# XTXBoard_2CPU.net
KiCad netlist of a schematic drawn in Altium Designer
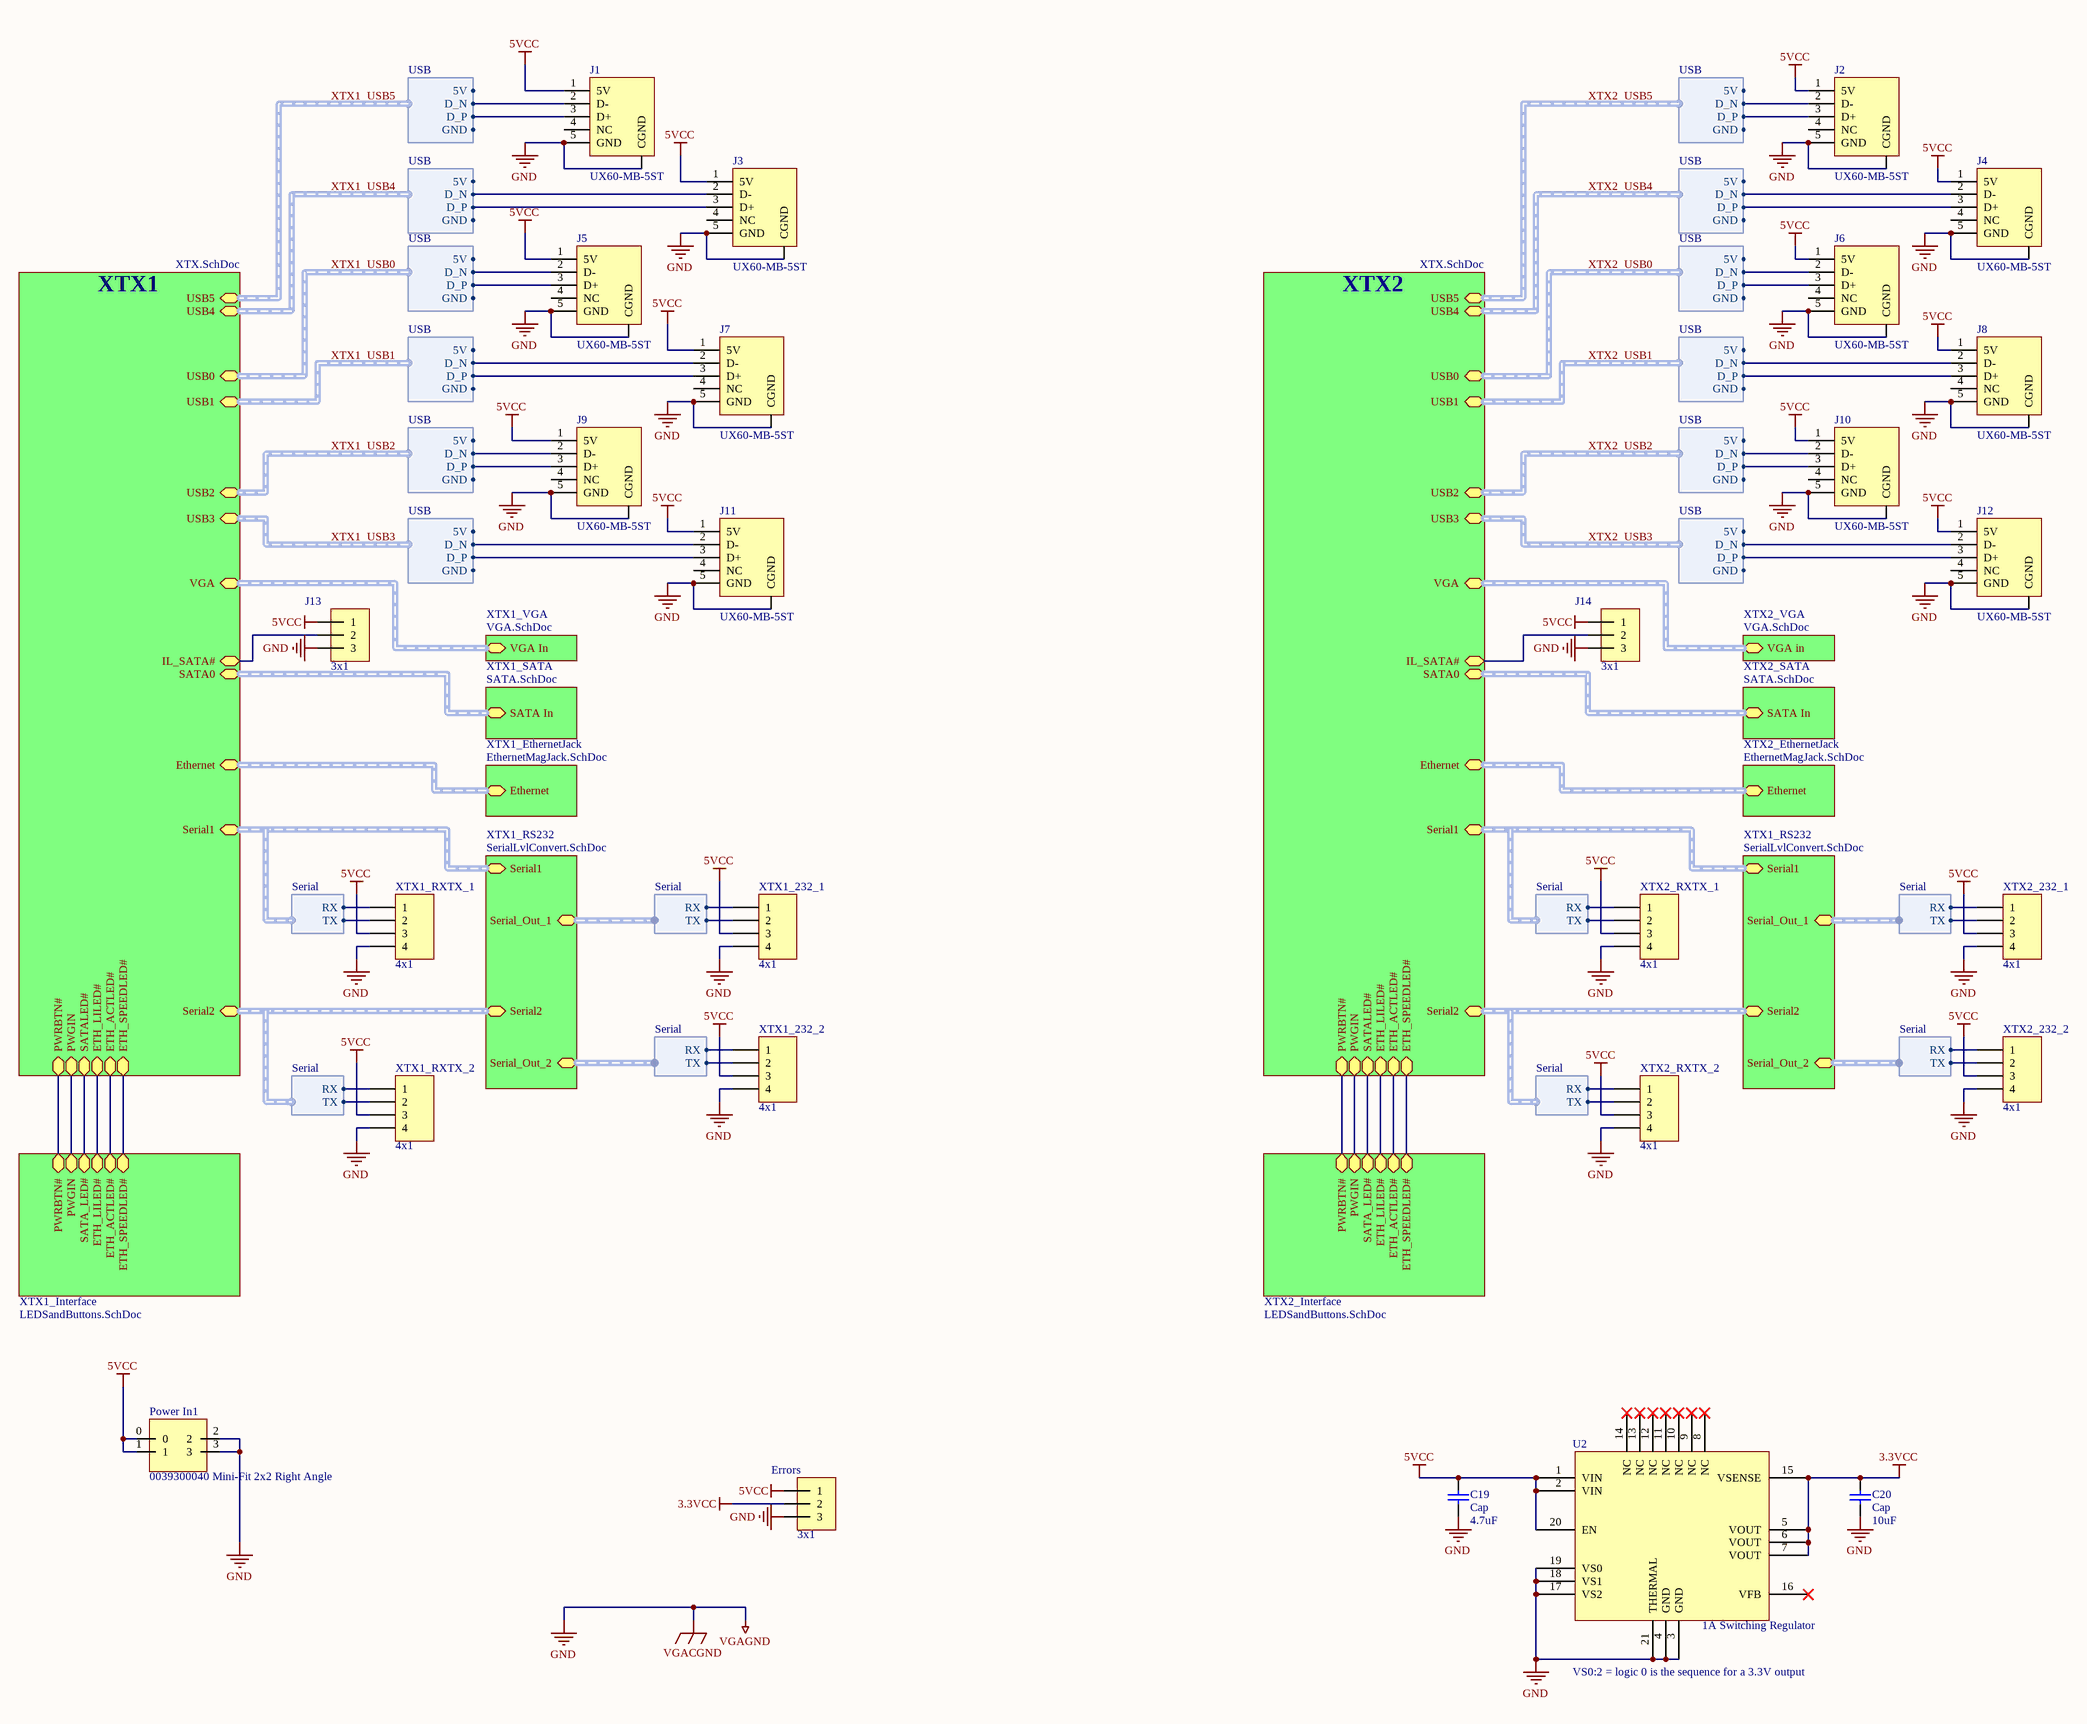
[diagram p0: XTXBoard(2CPU).SchDoc]

(export (version "E")
  (design (tool "Eeschema 10.0.6"))
  (components
    (comp (ref "C19")
      (value "Cap")
      (footprint "PassiveComponents:0805 (2012) Capacitor")
      (description "Capacitor")
      (fields (field (name "ALTIUM_VALUE") "4.7uF") (field (name "PUBLISHER") "Altium Limited"))
      (libsource (lib "Miscellaneous Devices") (part "Cap"))
    )
    (comp (ref "C20")
      (value "Cap")
      (footprint "PassiveComponents:1210 (3225) Capacitor")
      (description "Capacitor")
      (fields (field (name "ALTIUM_VALUE") "10uF") (field (name "PUBLISHER") "Altium Limited"))
      (libsource (lib "Miscellaneous Devices") (part "Cap"))
    )
    (comp (ref "Errors")
      (value "3x1")
      (footprint "Headers:Male 3x1")
      (description "3x1 100mil Header")
      (libsource (lib "Headers") (part "3x1"))
    )
    (comp (ref "J1")
      (value "UX60-MB-5ST")
      (footprint "Hirose:UX60-MB-5ST")
      (description "miniUSB Type B SMT Connector")
      (libsource (lib "Hirose") (part "UX60-MB-5ST"))
    )
    (comp (ref "J2")
      (value "UX60-MB-5ST")
      (footprint "Hirose:UX60-MB-5ST")
      (description "miniUSB Type B SMT Connector")
      (libsource (lib "Hirose") (part "UX60-MB-5ST"))
    )
    (comp (ref "J3")
      (value "UX60-MB-5ST")
      (footprint "Hirose:UX60-MB-5ST")
      (description "miniUSB Type B SMT Connector")
      (libsource (lib "Hirose") (part "UX60-MB-5ST"))
    )
    (comp (ref "J4")
      (value "UX60-MB-5ST")
      (footprint "Hirose:UX60-MB-5ST")
      (description "miniUSB Type B SMT Connector")
      (libsource (lib "Hirose") (part "UX60-MB-5ST"))
    )
    (comp (ref "J5")
      (value "UX60-MB-5ST")
      (footprint "Hirose:UX60-MB-5ST")
      (description "miniUSB Type B SMT Connector")
      (libsource (lib "Hirose") (part "UX60-MB-5ST"))
    )
    (comp (ref "J6")
      (value "UX60-MB-5ST")
      (footprint "Hirose:UX60-MB-5ST")
      (description "miniUSB Type B SMT Connector")
      (libsource (lib "Hirose") (part "UX60-MB-5ST"))
    )
    (comp (ref "J7")
      (value "UX60-MB-5ST")
      (footprint "Hirose:UX60-MB-5ST")
      (description "miniUSB Type B SMT Connector")
      (libsource (lib "Hirose") (part "UX60-MB-5ST"))
    )
    (comp (ref "J8")
      (value "UX60-MB-5ST")
      (footprint "Hirose:UX60-MB-5ST")
      (description "miniUSB Type B SMT Connector")
      (libsource (lib "Hirose") (part "UX60-MB-5ST"))
    )
    (comp (ref "J9")
      (value "UX60-MB-5ST")
      (footprint "Hirose:UX60-MB-5ST")
      (description "miniUSB Type B SMT Connector")
      (libsource (lib "Hirose") (part "UX60-MB-5ST"))
    )
    (comp (ref "J10")
      (value "UX60-MB-5ST")
      (footprint "Hirose:UX60-MB-5ST")
      (description "miniUSB Type B SMT Connector")
      (libsource (lib "Hirose") (part "UX60-MB-5ST"))
    )
    (comp (ref "J11")
      (value "UX60-MB-5ST")
      (footprint "Hirose:UX60-MB-5ST")
      (description "miniUSB Type B SMT Connector")
      (libsource (lib "Hirose") (part "UX60-MB-5ST"))
    )
    (comp (ref "J12")
      (value "UX60-MB-5ST")
      (footprint "Hirose:UX60-MB-5ST")
      (description "miniUSB Type B SMT Connector")
      (libsource (lib "Hirose") (part "UX60-MB-5ST"))
    )
    (comp (ref "J13")
      (value "3x1")
      (footprint "Headers:Male 3x1")
      (description "3x1 100mil Header")
      (libsource (lib "Headers") (part "3x1"))
    )
    (comp (ref "J14")
      (value "3x1")
      (footprint "Male 3x1")
      (description "3x1 100mil Header")
      (libsource (lib "Headers") (part "3x1"))
    )
    (comp (ref "Power In1")
      (value "0039300040 Mini-Fit 2x2 Right Angle")
      (footprint "Molex:0039300040 MINI-FIT JR 4-Pos Right Angle")
      (libsource (lib "Molex") (part "0039300040 Mini-Fit 2x2 Right Angle"))
    )
    (comp (ref "U2")
      (value "1A Switching Regulator")
      (footprint "QFN65P400X500X80-20N")
      (description "1A Step Down Voltage Converter")
      (fields (field (name "MANUFACTURER 1 PART NUMBER") "EN5311QI"))
      (libsource (lib "Enpirion") (part "Component_1"))
    )
    (comp (ref "XTX1_232_1")
      (value "4x1")
      (footprint "Male 4x1")
      (description "Header, 4-Pin")
      (fields (field (name "PUBLISHER") "Altium Limited"))
      (libsource (lib "Miscellaneous Connectors") (part "Header 4"))
    )
    (comp (ref "XTX1_232_2")
      (value "4x1")
      (footprint "Male 4x1")
      (description "Header, 4-Pin")
      (fields (field (name "PUBLISHER") "Altium Limited"))
      (libsource (lib "Miscellaneous Connectors") (part "Header 4"))
    )
    (comp (ref "XTX1_RXTX_1")
      (value "4x1")
      (footprint "Headers:Male 4x1")
      (description "Header, 4-Pin")
      (fields (field (name "PUBLISHER") "Altium Limited"))
      (libsource (lib "Miscellaneous Connectors") (part "Header 4"))
    )
    (comp (ref "XTX1_RXTX_2")
      (value "4x1")
      (footprint "Male 4x1")
      (description "Header, 4-Pin")
      (fields (field (name "PUBLISHER") "Altium Limited"))
      (libsource (lib "Miscellaneous Connectors") (part "Header 4"))
    )
    (comp (ref "XTX2_232_1")
      (value "4x1")
      (footprint "Male 4x1")
      (description "Header, 4-Pin")
      (fields (field (name "PUBLISHER") "Altium Limited"))
      (libsource (lib "Miscellaneous Connectors") (part "Header 4"))
    )
    (comp (ref "XTX2_232_2")
      (value "4x1")
      (footprint "Male 4x1")
      (description "Header, 4-Pin")
      (fields (field (name "PUBLISHER") "Altium Limited"))
      (libsource (lib "Miscellaneous Connectors") (part "Header 4"))
    )
    (comp (ref "XTX2_RXTX_1")
      (value "4x1")
      (footprint "Male 4x1")
      (description "Header, 4-Pin")
      (fields (field (name "PUBLISHER") "Altium Limited"))
      (libsource (lib "Miscellaneous Connectors") (part "Header 4"))
    )
    (comp (ref "XTX2_RXTX_2")
      (value "4x1")
      (footprint "Male 4x1")
      (description "Header, 4-Pin")
      (fields (field (name "PUBLISHER") "Altium Limited"))
      (libsource (lib "Miscellaneous Connectors") (part "Header 4"))
    )
  )
  (nets
    (net (code "22") (name "/IL_SATA#") (class "Default")
      (node (ref "J13") (pin "2") (pinfunction "2_2") (pintype "passive"))
    )
    (net (code "23") (name "/IL_SATA#_1") (class "Default")
      (node (ref "J14") (pin "2") (pinfunction "2_2") (pintype "passive"))
    )
    (net (code "51") (name "3.3VCC") (class "Default")
      (node (ref "C20") (pin "2") (pinfunction "2_2") (pintype "passive"))
      (node (ref "Errors") (pin "2") (pinfunction "2_2") (pintype "passive"))
      (node (ref "U2") (pin "15") (pinfunction "VSENSE_15") (pintype "passive"))
      (node (ref "U2") (pin "5") (pinfunction "VOUT_5") (pintype "passive"))
      (node (ref "U2") (pin "6") (pinfunction "VOUT_6") (pintype "passive"))
      (node (ref "U2") (pin "7") (pinfunction "VOUT_7") (pintype "passive"))
    )
    (net (code "52") (name "5VCC") (class "Default")
      (node (ref "C19") (pin "2") (pinfunction "2_2") (pintype "passive"))
      (node (ref "Errors") (pin "1") (pinfunction "1_1") (pintype "passive"))
      (node (ref "J1") (pin "1") (pinfunction "5V_1") (pintype "passive"))
      (node (ref "J10") (pin "1") (pinfunction "5V_1") (pintype "passive"))
      (node (ref "J11") (pin "1") (pinfunction "5V_1") (pintype "passive"))
      (node (ref "J12") (pin "1") (pinfunction "5V_1") (pintype "passive"))
      (node (ref "J13") (pin "1") (pinfunction "1_1") (pintype "passive"))
      (node (ref "J14") (pin "1") (pinfunction "1_1") (pintype "passive"))
      (node (ref "J2") (pin "1") (pinfunction "5V_1") (pintype "passive"))
      (node (ref "J3") (pin "1") (pinfunction "5V_1") (pintype "passive"))
      (node (ref "J4") (pin "1") (pinfunction "5V_1") (pintype "passive"))
      (node (ref "J5") (pin "1") (pinfunction "5V_1") (pintype "passive"))
      (node (ref "J6") (pin "1") (pinfunction "5V_1") (pintype "passive"))
      (node (ref "J7") (pin "1") (pinfunction "5V_1") (pintype "passive"))
      (node (ref "J8") (pin "1") (pinfunction "5V_1") (pintype "passive"))
      (node (ref "J9") (pin "1") (pinfunction "5V_1") (pintype "passive"))
      (node (ref "Power In1") (pin "0") (pinfunction "0_0") (pintype "passive"))
      (node (ref "Power In1") (pin "1") (pinfunction "1_1") (pintype "passive"))
      (node (ref "U2") (pin "1") (pinfunction "VIN_1") (pintype "passive"))
      (node (ref "U2") (pin "2") (pinfunction "VIN_2") (pintype "passive"))
      (node (ref "U2") (pin "20") (pinfunction "EN_20") (pintype "passive"))
      (node (ref "XTX1_232_1") (pin "3") (pinfunction "3_3") (pintype "passive"))
      (node (ref "XTX1_232_2") (pin "3") (pinfunction "3_3") (pintype "passive"))
      (node (ref "XTX1_RXTX_1") (pin "3") (pinfunction "3_3") (pintype "passive"))
      (node (ref "XTX1_RXTX_2") (pin "3") (pinfunction "3_3") (pintype "passive"))
      (node (ref "XTX2_232_1") (pin "3") (pinfunction "3_3") (pintype "passive"))
      (node (ref "XTX2_232_2") (pin "3") (pinfunction "3_3") (pintype "passive"))
      (node (ref "XTX2_RXTX_1") (pin "3") (pinfunction "3_3") (pintype "passive"))
      (node (ref "XTX2_RXTX_2") (pin "3") (pinfunction "3_3") (pintype "passive"))
    )
    (net (code "53") (name "GND") (class "Default")
      (node (ref "C19") (pin "1") (pinfunction "1_1") (pintype "passive"))
      (node (ref "C20") (pin "1") (pinfunction "1_1") (pintype "passive"))
      (node (ref "Errors") (pin "3") (pinfunction "3_3") (pintype "passive"))
      (node (ref "J1") (pin "5") (pinfunction "GND_5") (pintype "passive"))
      (node (ref "J1") (pin "CGND") (pinfunction "CGND_CGND") (pintype "passive"))
      (node (ref "J10") (pin "5") (pinfunction "GND_5") (pintype "passive"))
      (node (ref "J10") (pin "CGND") (pinfunction "CGND_CGND") (pintype "passive"))
      (node (ref "J11") (pin "5") (pinfunction "GND_5") (pintype "passive"))
      (node (ref "J11") (pin "CGND") (pinfunction "CGND_CGND") (pintype "passive"))
      (node (ref "J12") (pin "5") (pinfunction "GND_5") (pintype "passive"))
      (node (ref "J12") (pin "CGND") (pinfunction "CGND_CGND") (pintype "passive"))
      (node (ref "J13") (pin "3") (pinfunction "3_3") (pintype "passive"))
      (node (ref "J14") (pin "3") (pinfunction "3_3") (pintype "passive"))
      (node (ref "J2") (pin "5") (pinfunction "GND_5") (pintype "passive"))
      (node (ref "J2") (pin "CGND") (pinfunction "CGND_CGND") (pintype "passive"))
      (node (ref "J3") (pin "5") (pinfunction "GND_5") (pintype "passive"))
      (node (ref "J3") (pin "CGND") (pinfunction "CGND_CGND") (pintype "passive"))
      (node (ref "J4") (pin "5") (pinfunction "GND_5") (pintype "passive"))
      (node (ref "J4") (pin "CGND") (pinfunction "CGND_CGND") (pintype "passive"))
      (node (ref "J5") (pin "5") (pinfunction "GND_5") (pintype "passive"))
      (node (ref "J5") (pin "CGND") (pinfunction "CGND_CGND") (pintype "passive"))
      (node (ref "J6") (pin "5") (pinfunction "GND_5") (pintype "passive"))
      (node (ref "J6") (pin "CGND") (pinfunction "CGND_CGND") (pintype "passive"))
      (node (ref "J7") (pin "5") (pinfunction "GND_5") (pintype "passive"))
      (node (ref "J7") (pin "CGND") (pinfunction "CGND_CGND") (pintype "passive"))
      (node (ref "J8") (pin "5") (pinfunction "GND_5") (pintype "passive"))
      (node (ref "J8") (pin "CGND") (pinfunction "CGND_CGND") (pintype "passive"))
      (node (ref "J9") (pin "5") (pinfunction "GND_5") (pintype "passive"))
      (node (ref "J9") (pin "CGND") (pinfunction "CGND_CGND") (pintype "passive"))
      (node (ref "Power In1") (pin "2") (pinfunction "2_2") (pintype "passive"))
      (node (ref "Power In1") (pin "3") (pinfunction "3_3") (pintype "passive"))
      (node (ref "U2") (pin "17") (pinfunction "VS2_17") (pintype "passive"))
      (node (ref "U2") (pin "18") (pinfunction "VS1_18") (pintype "passive"))
      (node (ref "U2") (pin "19") (pinfunction "VS0_19") (pintype "passive"))
      (node (ref "U2") (pin "21") (pinfunction "THERMAL_21") (pintype "passive"))
      (node (ref "U2") (pin "3") (pinfunction "GND_3") (pintype "passive"))
      (node (ref "U2") (pin "4") (pinfunction "GND_4") (pintype "passive"))
      (node (ref "XTX1_232_1") (pin "4") (pinfunction "4_4") (pintype "passive"))
      (node (ref "XTX1_232_2") (pin "4") (pinfunction "4_4") (pintype "passive"))
      (node (ref "XTX1_RXTX_1") (pin "4") (pinfunction "4_4") (pintype "passive"))
      (node (ref "XTX1_RXTX_2") (pin "4") (pinfunction "4_4") (pintype "passive"))
      (node (ref "XTX2_232_1") (pin "4") (pinfunction "4_4") (pintype "passive"))
      (node (ref "XTX2_232_2") (pin "4") (pinfunction "4_4") (pintype "passive"))
      (node (ref "XTX2_RXTX_1") (pin "4") (pinfunction "4_4") (pintype "passive"))
      (node (ref "XTX2_RXTX_2") (pin "4") (pinfunction "4_4") (pintype "passive"))
    )
    (net (code "54") (name "unconnected-(J1-D+-Pad3)") (class "Default")
      (node (ref "J1") (pin "3") (pinfunction "D+_3") (pintype "passive"))
    )
    (net (code "55") (name "unconnected-(J1-D--Pad2)") (class "Default")
      (node (ref "J1") (pin "2") (pinfunction "D-_2") (pintype "passive"))
    )
    (net (code "56") (name "unconnected-(J1-NC-Pad4)") (class "Default")
      (node (ref "J1") (pin "4") (pinfunction "NC_4") (pintype "passive"))
    )
    (net (code "57") (name "unconnected-(J2-D+-Pad3)") (class "Default")
      (node (ref "J2") (pin "3") (pinfunction "D+_3") (pintype "passive"))
    )
    (net (code "58") (name "unconnected-(J2-D--Pad2)") (class "Default")
      (node (ref "J2") (pin "2") (pinfunction "D-_2") (pintype "passive"))
    )
    (net (code "59") (name "unconnected-(J2-NC-Pad4)") (class "Default")
      (node (ref "J2") (pin "4") (pinfunction "NC_4") (pintype "passive"))
    )
    (net (code "60") (name "unconnected-(J3-D+-Pad3)") (class "Default")
      (node (ref "J3") (pin "3") (pinfunction "D+_3") (pintype "passive"))
    )
    (net (code "61") (name "unconnected-(J3-D--Pad2)") (class "Default")
      (node (ref "J3") (pin "2") (pinfunction "D-_2") (pintype "passive"))
    )
    (net (code "62") (name "unconnected-(J3-NC-Pad4)") (class "Default")
      (node (ref "J3") (pin "4") (pinfunction "NC_4") (pintype "passive"))
    )
    (net (code "63") (name "unconnected-(J4-D+-Pad3)") (class "Default")
      (node (ref "J4") (pin "3") (pinfunction "D+_3") (pintype "passive"))
    )
    (net (code "64") (name "unconnected-(J4-D--Pad2)") (class "Default")
      (node (ref "J4") (pin "2") (pinfunction "D-_2") (pintype "passive"))
    )
    (net (code "65") (name "unconnected-(J4-NC-Pad4)") (class "Default")
      (node (ref "J4") (pin "4") (pinfunction "NC_4") (pintype "passive"))
    )
    (net (code "66") (name "unconnected-(J5-D+-Pad3)") (class "Default")
      (node (ref "J5") (pin "3") (pinfunction "D+_3") (pintype "passive"))
    )
    (net (code "67") (name "unconnected-(J5-D--Pad2)") (class "Default")
      (node (ref "J5") (pin "2") (pinfunction "D-_2") (pintype "passive"))
    )
    (net (code "68") (name "unconnected-(J5-NC-Pad4)") (class "Default")
      (node (ref "J5") (pin "4") (pinfunction "NC_4") (pintype "passive"))
    )
    (net (code "69") (name "unconnected-(J6-D+-Pad3)") (class "Default")
      (node (ref "J6") (pin "3") (pinfunction "D+_3") (pintype "passive"))
    )
    (net (code "70") (name "unconnected-(J6-D--Pad2)") (class "Default")
      (node (ref "J6") (pin "2") (pinfunction "D-_2") (pintype "passive"))
    )
    (net (code "71") (name "unconnected-(J6-NC-Pad4)") (class "Default")
      (node (ref "J6") (pin "4") (pinfunction "NC_4") (pintype "passive"))
    )
    (net (code "72") (name "unconnected-(J7-D+-Pad3)") (class "Default")
      (node (ref "J7") (pin "3") (pinfunction "D+_3") (pintype "passive"))
    )
    (net (code "73") (name "unconnected-(J7-D--Pad2)") (class "Default")
      (node (ref "J7") (pin "2") (pinfunction "D-_2") (pintype "passive"))
    )
    (net (code "74") (name "unconnected-(J7-NC-Pad4)") (class "Default")
      (node (ref "J7") (pin "4") (pinfunction "NC_4") (pintype "passive"))
    )
    (net (code "75") (name "unconnected-(J8-D+-Pad3)") (class "Default")
      (node (ref "J8") (pin "3") (pinfunction "D+_3") (pintype "passive"))
    )
    (net (code "76") (name "unconnected-(J8-D--Pad2)") (class "Default")
      (node (ref "J8") (pin "2") (pinfunction "D-_2") (pintype "passive"))
    )
    (net (code "77") (name "unconnected-(J8-NC-Pad4)") (class "Default")
      (node (ref "J8") (pin "4") (pinfunction "NC_4") (pintype "passive"))
    )
    (net (code "78") (name "unconnected-(J9-D+-Pad3)") (class "Default")
      (node (ref "J9") (pin "3") (pinfunction "D+_3") (pintype "passive"))
    )
    (net (code "79") (name "unconnected-(J9-D--Pad2)") (class "Default")
      (node (ref "J9") (pin "2") (pinfunction "D-_2") (pintype "passive"))
    )
    (net (code "80") (name "unconnected-(J9-NC-Pad4)") (class "Default")
      (node (ref "J9") (pin "4") (pinfunction "NC_4") (pintype "passive"))
    )
    (net (code "81") (name "unconnected-(J10-D+-Pad3)") (class "Default")
      (node (ref "J10") (pin "3") (pinfunction "D+_3") (pintype "passive"))
    )
    (net (code "82") (name "unconnected-(J10-D--Pad2)") (class "Default")
      (node (ref "J10") (pin "2") (pinfunction "D-_2") (pintype "passive"))
    )
    (net (code "83") (name "unconnected-(J10-NC-Pad4)") (class "Default")
      (node (ref "J10") (pin "4") (pinfunction "NC_4") (pintype "passive"))
    )
    (net (code "84") (name "unconnected-(J11-D+-Pad3)") (class "Default")
      (node (ref "J11") (pin "3") (pinfunction "D+_3") (pintype "passive"))
    )
    (net (code "85") (name "unconnected-(J11-D--Pad2)") (class "Default")
      (node (ref "J11") (pin "2") (pinfunction "D-_2") (pintype "passive"))
    )
    (net (code "86") (name "unconnected-(J11-NC-Pad4)") (class "Default")
      (node (ref "J11") (pin "4") (pinfunction "NC_4") (pintype "passive"))
    )
    (net (code "87") (name "unconnected-(J12-D+-Pad3)") (class "Default")
      (node (ref "J12") (pin "3") (pinfunction "D+_3") (pintype "passive"))
    )
    (net (code "88") (name "unconnected-(J12-D--Pad2)") (class "Default")
      (node (ref "J12") (pin "2") (pinfunction "D-_2") (pintype "passive"))
    )
    (net (code "89") (name "unconnected-(J12-NC-Pad4)") (class "Default")
      (node (ref "J12") (pin "4") (pinfunction "NC_4") (pintype "passive"))
    )
    (net (code "90") (name "unconnected-(U2-NC-Pad8)") (class "Default")
      (node (ref "U2") (pin "8") (pinfunction "NC_8") (pintype "passive+no_connect"))
    )
    (net (code "91") (name "unconnected-(U2-NC-Pad9)") (class "Default")
      (node (ref "U2") (pin "9") (pinfunction "NC_9") (pintype "passive+no_connect"))
    )
    (net (code "92") (name "unconnected-(U2-NC-Pad10)") (class "Default")
      (node (ref "U2") (pin "10") (pinfunction "NC_10") (pintype "passive+no_connect"))
    )
    (net (code "93") (name "unconnected-(U2-NC-Pad11)") (class "Default")
      (node (ref "U2") (pin "11") (pinfunction "NC_11") (pintype "passive+no_connect"))
    )
    (net (code "94") (name "unconnected-(U2-NC-Pad12)") (class "Default")
      (node (ref "U2") (pin "12") (pinfunction "NC_12") (pintype "passive+no_connect"))
    )
    (net (code "95") (name "unconnected-(U2-NC-Pad13)") (class "Default")
      (node (ref "U2") (pin "13") (pinfunction "NC_13") (pintype "passive+no_connect"))
    )
    (net (code "96") (name "unconnected-(U2-NC-Pad14)") (class "Default")
      (node (ref "U2") (pin "14") (pinfunction "NC_14") (pintype "passive+no_connect"))
    )
    (net (code "97") (name "unconnected-(U2-VFB-Pad16)") (class "Default")
      (node (ref "U2") (pin "16") (pinfunction "VFB_16") (pintype "passive+no_connect"))
    )
    (net (code "98") (name "unconnected-(XTX1_232_1-Pad1)") (class "Default")
      (node (ref "XTX1_232_1") (pin "1") (pinfunction "1_1") (pintype "passive"))
    )
    (net (code "99") (name "unconnected-(XTX1_232_1-Pad2)") (class "Default")
      (node (ref "XTX1_232_1") (pin "2") (pinfunction "2_2") (pintype "passive"))
    )
    (net (code "100") (name "unconnected-(XTX1_232_2-Pad1)") (class "Default")
      (node (ref "XTX1_232_2") (pin "1") (pinfunction "1_1") (pintype "passive"))
    )
    (net (code "101") (name "unconnected-(XTX1_232_2-Pad2)") (class "Default")
      (node (ref "XTX1_232_2") (pin "2") (pinfunction "2_2") (pintype "passive"))
    )
    (net (code "102") (name "unconnected-(XTX1_RXTX_1-Pad1)") (class "Default")
      (node (ref "XTX1_RXTX_1") (pin "1") (pinfunction "1_1") (pintype "passive"))
    )
    (net (code "103") (name "unconnected-(XTX1_RXTX_1-Pad2)") (class "Default")
      (node (ref "XTX1_RXTX_1") (pin "2") (pinfunction "2_2") (pintype "passive"))
    )
    (net (code "104") (name "unconnected-(XTX1_RXTX_2-Pad1)") (class "Default")
      (node (ref "XTX1_RXTX_2") (pin "1") (pinfunction "1_1") (pintype "passive"))
    )
    (net (code "105") (name "unconnected-(XTX1_RXTX_2-Pad2)") (class "Default")
      (node (ref "XTX1_RXTX_2") (pin "2") (pinfunction "2_2") (pintype "passive"))
    )
    (net (code "106") (name "unconnected-(XTX2_232_1-Pad1)") (class "Default")
      (node (ref "XTX2_232_1") (pin "1") (pinfunction "1_1") (pintype "passive"))
    )
    (net (code "107") (name "unconnected-(XTX2_232_1-Pad2)") (class "Default")
      (node (ref "XTX2_232_1") (pin "2") (pinfunction "2_2") (pintype "passive"))
    )
    (net (code "108") (name "unconnected-(XTX2_232_2-Pad1)") (class "Default")
      (node (ref "XTX2_232_2") (pin "1") (pinfunction "1_1") (pintype "passive"))
    )
    (net (code "109") (name "unconnected-(XTX2_232_2-Pad2)") (class "Default")
      (node (ref "XTX2_232_2") (pin "2") (pinfunction "2_2") (pintype "passive"))
    )
    (net (code "110") (name "unconnected-(XTX2_RXTX_1-Pad1)") (class "Default")
      (node (ref "XTX2_RXTX_1") (pin "1") (pinfunction "1_1") (pintype "passive"))
    )
    (net (code "111") (name "unconnected-(XTX2_RXTX_1-Pad2)") (class "Default")
      (node (ref "XTX2_RXTX_1") (pin "2") (pinfunction "2_2") (pintype "passive"))
    )
    (net (code "112") (name "unconnected-(XTX2_RXTX_2-Pad1)") (class "Default")
      (node (ref "XTX2_RXTX_2") (pin "1") (pinfunction "1_1") (pintype "passive"))
    )
    (net (code "113") (name "unconnected-(XTX2_RXTX_2-Pad2)") (class "Default")
      (node (ref "XTX2_RXTX_2") (pin "2") (pinfunction "2_2") (pintype "passive"))
    )
  )
)
